# dds.net
KiCad netlist of a schematic drawn in EAGLE
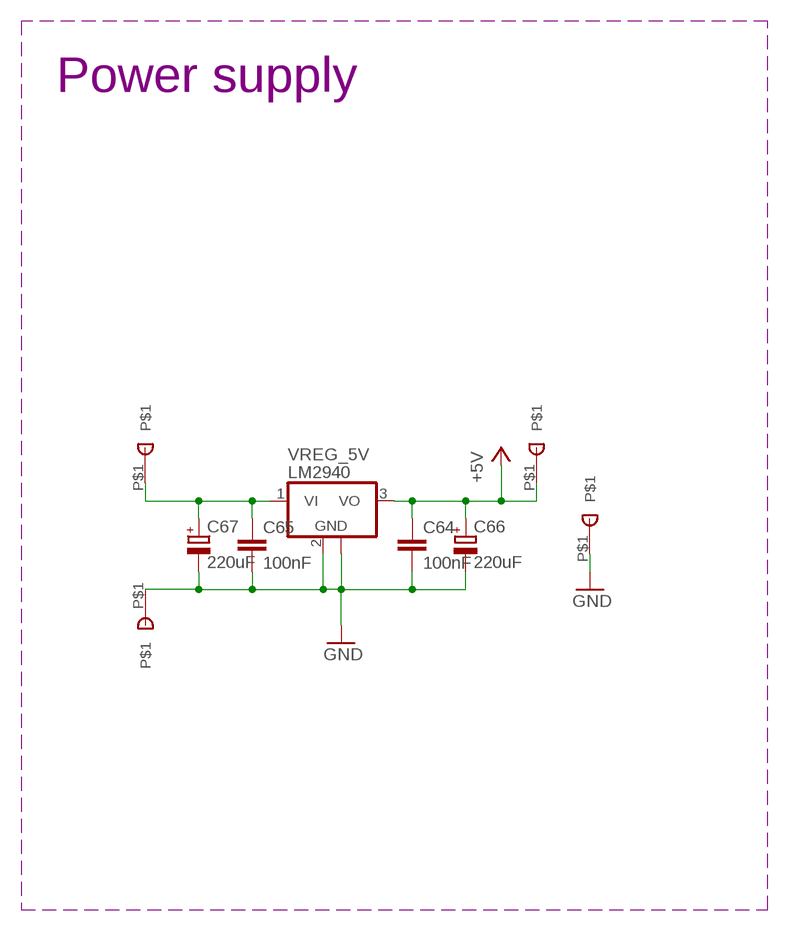
[diagram p0: schematic, sheet 1]
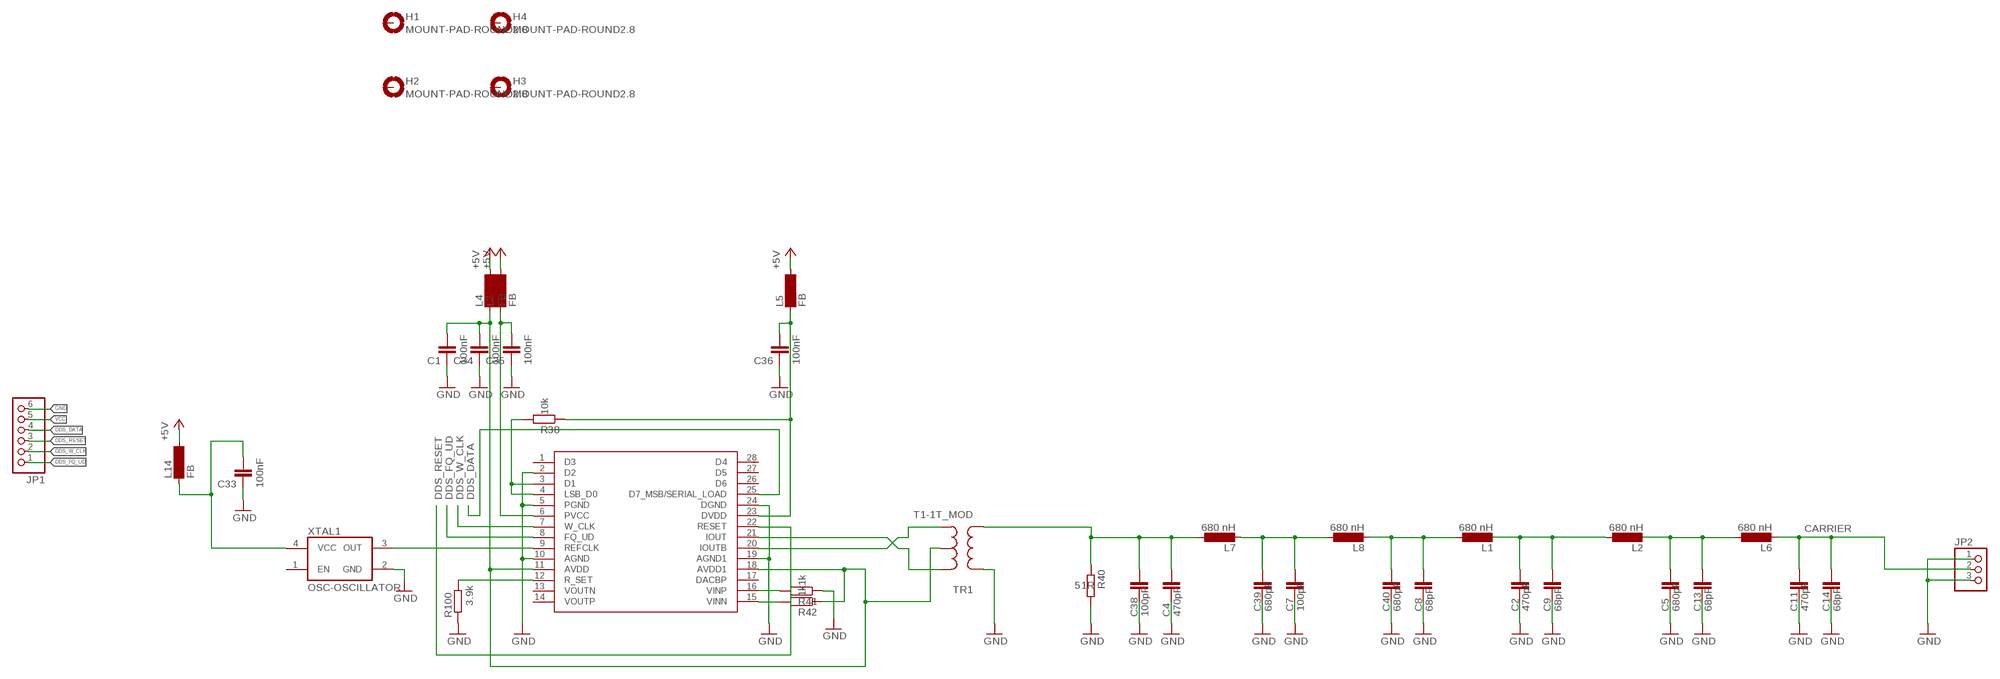
[diagram p1: schematic, sheet 2]

(export (version "E")
  (design (tool "Eeschema 10.0.6"))
  (components
    (comp (ref "C64")
      (value "100nF")
      (footprint "eagle-import:C0603")
      (libsource (lib "eagle-import") (part "C-EUC0603"))
    )
    (comp (ref "C65")
      (value "100nF")
      (footprint "eagle-import:C0603")
      (libsource (lib "eagle-import") (part "C-EUC0603"))
    )
    (comp (ref "C66")
      (value "220uF")
      (footprint "eagle-import:CT7343")
      (libsource (lib "eagle-import") (part "CPOL-EUCT7343"))
    )
    (comp (ref "C67")
      (value "220uF")
      (footprint "eagle-import:CT7343")
      (libsource (lib "eagle-import") (part "CPOL-EUCT7343"))
    )
    (comp (ref "U$3")
      (value "SINGLE_SMD_CONN_2.5X3.5")
      (footprint "eagle-import:SMD_CONN_2.5X3.5")
      (libsource (lib "eagle-import") (part "SINGLE_SMD_CONN_2.5X3.5"))
    )
    (comp (ref "U$8")
      (value "SINGLE_SMD_CONN_2.5X3.5")
      (footprint "eagle-import:SMD_CONN_2.5X3.5")
      (libsource (lib "eagle-import") (part "SINGLE_SMD_CONN_2.5X3.5"))
    )
    (comp (ref "U$22")
      (value "SINGLE_SMD_CONN_1.5X1.5")
      (footprint "eagle-import:SMD_CONN_1.5X1.5")
      (libsource (lib "eagle-import") (part "SINGLE_SMD_CONN_1.5X1.5"))
    )
    (comp (ref "U$23")
      (value "SINGLE_SMD_CONN_1.5X1.5")
      (footprint "eagle-import:SMD_CONN_1.5X1.5")
      (libsource (lib "eagle-import") (part "SINGLE_SMD_CONN_1.5X1.5"))
    )
    (comp (ref "VREG_5V")
      (value "LM2940")
      (footprint "eagle-import:SOT223")
      (libsource (lib "eagle-import") (part "UA78MDCY05"))
    )
    (comp (ref "C1")
      (value "100nF")
      (footprint "eagle-import:C0603K")
      (libsource (lib "eagle-import") (part "C-EUC0603K"))
    )
    (comp (ref "C2")
      (value "470pF")
      (footprint "eagle-import:C1206")
      (libsource (lib "eagle-import") (part "C-EUC1206"))
    )
    (comp (ref "C4")
      (value "470pF")
      (footprint "eagle-import:C1206")
      (libsource (lib "eagle-import") (part "C-EUC1206"))
    )
    (comp (ref "C5")
      (value "680pF")
      (footprint "eagle-import:C1206")
      (libsource (lib "eagle-import") (part "C-EUC1206"))
    )
    (comp (ref "C7")
      (value "100pF")
      (footprint "eagle-import:C1206")
      (libsource (lib "eagle-import") (part "C-EUC1206"))
    )
    (comp (ref "C8")
      (value "68pF")
      (footprint "eagle-import:C1206")
      (libsource (lib "eagle-import") (part "C-EUC1206"))
    )
    (comp (ref "C9")
      (value "68pF")
      (footprint "eagle-import:C1206")
      (libsource (lib "eagle-import") (part "C-EUC1206"))
    )
    (comp (ref "C11")
      (value "470pF")
      (footprint "eagle-import:C1206")
      (libsource (lib "eagle-import") (part "C-EUC1206"))
    )
    (comp (ref "C13")
      (value "68pF")
      (footprint "eagle-import:C1206")
      (libsource (lib "eagle-import") (part "C-EUC1206"))
    )
    (comp (ref "C14")
      (value "68pF")
      (footprint "eagle-import:C1206")
      (libsource (lib "eagle-import") (part "C-EUC1206"))
    )
    (comp (ref "C33")
      (value "100nF")
      (footprint "eagle-import:C0603K")
      (libsource (lib "eagle-import") (part "C-EUC0603K"))
    )
    (comp (ref "C34")
      (value "100nF")
      (footprint "eagle-import:C0603K")
      (libsource (lib "eagle-import") (part "C-EUC0603K"))
    )
    (comp (ref "C35")
      (value "100nF")
      (footprint "eagle-import:C0603K")
      (libsource (lib "eagle-import") (part "C-EUC0603K"))
    )
    (comp (ref "C36")
      (value "100nF")
      (footprint "eagle-import:C0603K")
      (libsource (lib "eagle-import") (part "C-EUC0603K"))
    )
    (comp (ref "C38")
      (value "100pF")
      (footprint "eagle-import:C1206")
      (libsource (lib "eagle-import") (part "C-EUC1206"))
    )
    (comp (ref "C39")
      (value "680pF")
      (footprint "eagle-import:C1206")
      (libsource (lib "eagle-import") (part "C-EUC1206"))
    )
    (comp (ref "C40")
      (value "680pF")
      (footprint "eagle-import:C1206")
      (libsource (lib "eagle-import") (part "C-EUC1206"))
    )
    (comp (ref "H1")
      (value "MOUNT-PAD-ROUND2.8")
      (footprint "eagle-import:2,8-PAD")
      (libsource (lib "eagle-import") (part "MOUNT-PAD-ROUND2.8"))
    )
    (comp (ref "H2")
      (value "MOUNT-PAD-ROUND2.8")
      (footprint "eagle-import:2,8-PAD")
      (libsource (lib "eagle-import") (part "MOUNT-PAD-ROUND2.8"))
    )
    (comp (ref "H3")
      (value "MOUNT-PAD-ROUND2.8")
      (footprint "eagle-import:2,8-PAD")
      (libsource (lib "eagle-import") (part "MOUNT-PAD-ROUND2.8"))
    )
    (comp (ref "H4")
      (value "MOUNT-PAD-ROUND2.8")
      (footprint "eagle-import:2,8-PAD")
      (libsource (lib "eagle-import") (part "MOUNT-PAD-ROUND2.8"))
    )
    (comp (ref "JP1")
      (value "PINHD-1X6")
      (footprint "eagle-import:1X06")
      (libsource (lib "eagle-import") (part "PINHD-1X6"))
    )
    (comp (ref "JP2")
      (value "PINHD-1X3")
      (footprint "eagle-import:1X03")
      (libsource (lib "eagle-import") (part "PINHD-1X3"))
    )
    (comp (ref "L1")
      (value "680 nH")
      (footprint "eagle-import:L1812")
      (libsource (lib "eagle-import") (part "L-EUL1812"))
    )
    (comp (ref "L2")
      (value "680 nH")
      (footprint "eagle-import:L1812")
      (libsource (lib "eagle-import") (part "L-EUL1812"))
    )
    (comp (ref "L3")
      (value "FB")
      (footprint "eagle-import:SM-1206")
      (libsource (lib "eagle-import") (part "SM-1206"))
    )
    (comp (ref "L4")
      (value "FB")
      (footprint "eagle-import:SM-1206")
      (libsource (lib "eagle-import") (part "SM-1206"))
    )
    (comp (ref "L5")
      (value "FB")
      (footprint "eagle-import:SM-1206")
      (libsource (lib "eagle-import") (part "SM-1206"))
    )
    (comp (ref "L6")
      (value "680 nH")
      (footprint "eagle-import:L1812")
      (libsource (lib "eagle-import") (part "L-EUL1812"))
    )
    (comp (ref "L7")
      (value "680 nH")
      (footprint "eagle-import:L1812")
      (libsource (lib "eagle-import") (part "L-EUL1812"))
    )
    (comp (ref "L8")
      (value "680 nH")
      (footprint "eagle-import:L1812")
      (libsource (lib "eagle-import") (part "L-EUL1812"))
    )
    (comp (ref "L14")
      (value "FB")
      (footprint "eagle-import:SM-1206")
      (libsource (lib "eagle-import") (part "SM-1206"))
    )
    (comp (ref "R38")
      (value "10k")
      (footprint "eagle-import:R0603")
      (libsource (lib "eagle-import") (part "R-EU_R0603"))
    )
    (comp (ref "R40")
      (value "51R")
      (footprint "eagle-import:R0603")
      (libsource (lib "eagle-import") (part "R-EU_R0603"))
    )
    (comp (ref "R41")
      (value "1k")
      (footprint "eagle-import:R0603")
      (libsource (lib "eagle-import") (part "R-EU_R0603"))
    )
    (comp (ref "R42")
      (value "1k")
      (footprint "eagle-import:R0603")
      (libsource (lib "eagle-import") (part "R-EU_R0603"))
    )
    (comp (ref "R100")
      (value "3.9k")
      (footprint "eagle-import:R0603")
      (libsource (lib "eagle-import") (part "R-EU_R0603"))
    )
    (comp (ref "TR1")
      (value "T1-1T_MOD")
      (footprint "eagle-import:KK81_MOD")
      (libsource (lib "eagle-import") (part "T1-1T_MOD"))
    )
    (comp (ref "U$9")
      (value "AD9851BR")
      (footprint "eagle-import:TSSOP28")
      (libsource (lib "eagle-import") (part "AD9851BR"))
    )
    (comp (ref "XTAL1")
      (value "OSC-OSCILLATOR")
      (footprint "eagle-import:OSCILLATOR_7X5_SMD")
      (libsource (lib "eagle-import") (part "OSC-OSCILLATOR"))
    )
  )
  (nets
    (net (code "1") (name "+5V") (class "Default")
      (node (ref "C64") (pin "1") (pinfunction "1_1") (pintype "passive"))
      (node (ref "C66") (pin "+") (pinfunction "+_+") (pintype "passive"))
      (node (ref "L14") (pin "2") (pinfunction "2_2") (pintype "passive"))
      (node (ref "L3") (pin "2") (pinfunction "2_2") (pintype "passive"))
      (node (ref "L4") (pin "2") (pinfunction "2_2") (pintype "passive"))
      (node (ref "L5") (pin "2") (pinfunction "2_2") (pintype "passive"))
      (node (ref "U$22") (pin "P$1") (pinfunction "P$1_P$1") (pintype "bidirectional"))
      (node (ref "VREG_5V") (pin "3") (pinfunction "VO_3") (pintype "passive"))
    )
    (net (code "2") (name "DDS_DATA") (class "Default")
      (node (ref "JP1") (pin "4") (pinfunction "4_4") (pintype "passive"))
      (node (ref "U$9") (pin "25") (pinfunction "D7_MSB/SERIAL_LOAD_25") (pintype "bidirectional"))
    )
    (net (code "3") (name "DDS_FQ_UD") (class "Default")
      (node (ref "JP1") (pin "1") (pinfunction "1_1") (pintype "passive"))
      (node (ref "U$9") (pin "8") (pinfunction "FQ_UD_8") (pintype "bidirectional"))
    )
    (net (code "4") (name "DDS_RESET") (class "Default")
      (node (ref "JP1") (pin "3") (pinfunction "3_3") (pintype "passive"))
      (node (ref "U$9") (pin "22") (pinfunction "RESET_22") (pintype "bidirectional"))
    )
    (net (code "5") (name "DDS_W_CLK") (class "Default")
      (node (ref "JP1") (pin "2") (pinfunction "2_2") (pintype "passive"))
      (node (ref "U$9") (pin "7") (pinfunction "W_CLK_7") (pintype "bidirectional"))
    )
    (net (code "6") (name "GND") (class "Default")
      (node (ref "C1") (pin "1") (pinfunction "1_1") (pintype "passive"))
      (node (ref "C11") (pin "1") (pinfunction "1_1") (pintype "passive"))
      (node (ref "C13") (pin "1") (pinfunction "1_1") (pintype "passive"))
      (node (ref "C14") (pin "1") (pinfunction "1_1") (pintype "passive"))
      (node (ref "C2") (pin "1") (pinfunction "1_1") (pintype "passive"))
      (node (ref "C33") (pin "1") (pinfunction "1_1") (pintype "passive"))
      (node (ref "C34") (pin "1") (pinfunction "1_1") (pintype "passive"))
      (node (ref "C35") (pin "1") (pinfunction "1_1") (pintype "passive"))
      (node (ref "C36") (pin "1") (pinfunction "1_1") (pintype "passive"))
      (node (ref "C38") (pin "1") (pinfunction "1_1") (pintype "passive"))
      (node (ref "C39") (pin "1") (pinfunction "1_1") (pintype "passive"))
      (node (ref "C4") (pin "1") (pinfunction "1_1") (pintype "passive"))
      (node (ref "C40") (pin "1") (pinfunction "1_1") (pintype "passive"))
      (node (ref "C5") (pin "1") (pinfunction "1_1") (pintype "passive"))
      (node (ref "C64") (pin "2") (pinfunction "2_2") (pintype "passive"))
      (node (ref "C65") (pin "2") (pinfunction "2_2") (pintype "passive"))
      (node (ref "C66") (pin "-") (pinfunction "-_-") (pintype "passive"))
      (node (ref "C67") (pin "-") (pinfunction "-_-") (pintype "passive"))
      (node (ref "C7") (pin "1") (pinfunction "1_1") (pintype "passive"))
      (node (ref "C8") (pin "1") (pinfunction "1_1") (pintype "passive"))
      (node (ref "C9") (pin "1") (pinfunction "1_1") (pintype "passive"))
      (node (ref "JP1") (pin "6") (pinfunction "6_6") (pintype "passive"))
      (node (ref "JP2") (pin "1") (pinfunction "1_1") (pintype "passive"))
      (node (ref "JP2") (pin "3") (pinfunction "3_3") (pintype "passive"))
      (node (ref "R100") (pin "1") (pinfunction "1_1") (pintype "passive"))
      (node (ref "R40") (pin "2") (pinfunction "2_2") (pintype "passive"))
      (node (ref "R41") (pin "1") (pinfunction "1_1") (pintype "passive"))
      (node (ref "TR1") (pin "1") (pinfunction "P1_1") (pintype "passive"))
      (node (ref "U$23") (pin "P$1") (pinfunction "P$1_P$1") (pintype "bidirectional"))
      (node (ref "U$3") (pin "P$1") (pinfunction "P$1_P$1") (pintype "bidirectional"))
      (node (ref "U$9") (pin "10") (pinfunction "AGND_10") (pintype "bidirectional"))
      (node (ref "U$9") (pin "19") (pinfunction "AGND1_19") (pintype "bidirectional"))
      (node (ref "U$9") (pin "2") (pinfunction "D2_2") (pintype "bidirectional"))
      (node (ref "U$9") (pin "24") (pinfunction "DGND_24") (pintype "bidirectional"))
      (node (ref "U$9") (pin "5") (pinfunction "PGND_5") (pintype "bidirectional"))
      (node (ref "VREG_5V") (pin "2") (pinfunction "GND_2") (pintype "passive"))
      (node (ref "VREG_5V") (pin "4") (pinfunction "GND_4") (pintype "passive"))
      (node (ref "XTAL1") (pin "2") (pinfunction "GND_2") (pintype "power_in"))
    )
    (net (code "7") (name "Net-(C2-Pad2)") (class "Default")
      (node (ref "C2") (pin "2") (pinfunction "2_2") (pintype "passive"))
      (node (ref "C9") (pin "2") (pinfunction "2_2") (pintype "passive"))
      (node (ref "L1") (pin "2") (pinfunction "2_2") (pintype "passive"))
      (node (ref "L2") (pin "1") (pinfunction "1_1") (pintype "passive"))
    )
    (net (code "8") (name "Net-(C11-Pad2)") (class "Default")
      (node (ref "C11") (pin "2") (pinfunction "2_2") (pintype "passive"))
      (node (ref "C14") (pin "2") (pinfunction "2_2") (pintype "passive"))
      (node (ref "JP2") (pin "2") (pinfunction "2_2") (pintype "passive"))
      (node (ref "L6") (pin "2") (pinfunction "2_2") (pintype "passive"))
    )
    (net (code "9") (name "Net-(C13-Pad2)") (class "Default")
      (node (ref "C13") (pin "2") (pinfunction "2_2") (pintype "passive"))
      (node (ref "C5") (pin "2") (pinfunction "2_2") (pintype "passive"))
      (node (ref "L2") (pin "2") (pinfunction "2_2") (pintype "passive"))
      (node (ref "L6") (pin "1") (pinfunction "1_1") (pintype "passive"))
    )
    (net (code "10") (name "Net-(C39-Pad2)") (class "Default")
      (node (ref "C39") (pin "2") (pinfunction "2_2") (pintype "passive"))
      (node (ref "C7") (pin "2") (pinfunction "2_2") (pintype "passive"))
      (node (ref "L7") (pin "2") (pinfunction "2_2") (pintype "passive"))
      (node (ref "L8") (pin "1") (pinfunction "1_1") (pintype "passive"))
    )
    (net (code "11") (name "Net-(C40-Pad2)") (class "Default")
      (node (ref "C40") (pin "2") (pinfunction "2_2") (pintype "passive"))
      (node (ref "C8") (pin "2") (pinfunction "2_2") (pintype "passive"))
      (node (ref "L1") (pin "1") (pinfunction "1_1") (pintype "passive"))
      (node (ref "L8") (pin "2") (pinfunction "2_2") (pintype "passive"))
    )
    (net (code "12") (name "Net-(TR1-P2)") (class "Default")
      (node (ref "C38") (pin "2") (pinfunction "2_2") (pintype "passive"))
      (node (ref "C4") (pin "2") (pinfunction "2_2") (pintype "passive"))
      (node (ref "L7") (pin "1") (pinfunction "1_1") (pintype "passive"))
      (node (ref "R40") (pin "1") (pinfunction "1_1") (pintype "passive"))
      (node (ref "TR1") (pin "3") (pinfunction "P2_3") (pintype "passive"))
    )
    (net (code "13") (name "Net-(TR1-S1)") (class "Default")
      (node (ref "TR1") (pin "6") (pinfunction "S1_6") (pintype "passive"))
      (node (ref "U$9") (pin "21") (pinfunction "IOUT_21") (pintype "bidirectional"))
    )
    (net (code "14") (name "Net-(TR1-S2)") (class "Default")
      (node (ref "TR1") (pin "4") (pinfunction "S2_4") (pintype "passive"))
      (node (ref "U$9") (pin "20") (pinfunction "IOUTB_20") (pintype "bidirectional"))
    )
    (net (code "15") (name "Net-(TR1-ST)") (class "Default")
      (node (ref "C1") (pin "2") (pinfunction "2_2") (pintype "passive"))
      (node (ref "C34") (pin "2") (pinfunction "2_2") (pintype "passive"))
      (node (ref "L4") (pin "1") (pinfunction "1_1") (pintype "passive"))
      (node (ref "R42") (pin "1") (pinfunction "1_1") (pintype "passive"))
      (node (ref "TR1") (pin "5") (pinfunction "ST_5") (pintype "passive"))
      (node (ref "U$9") (pin "11") (pinfunction "AVDD_11") (pintype "bidirectional"))
      (node (ref "U$9") (pin "18") (pinfunction "AVDD1_18") (pintype "bidirectional"))
    )
    (net (code "16") (name "Net-(U$9-D1)") (class "Default")
      (node (ref "R38") (pin "2") (pinfunction "2_2") (pintype "passive"))
      (node (ref "U$9") (pin "3") (pinfunction "D1_3") (pintype "bidirectional"))
      (node (ref "U$9") (pin "4") (pinfunction "LSB_D0_4") (pintype "bidirectional"))
    )
    (net (code "17") (name "Net-(U$9-DVDD)") (class "Default")
      (node (ref "C36") (pin "2") (pinfunction "2_2") (pintype "passive"))
      (node (ref "L5") (pin "1") (pinfunction "1_1") (pintype "passive"))
      (node (ref "R38") (pin "1") (pinfunction "1_1") (pintype "passive"))
      (node (ref "U$9") (pin "23") (pinfunction "DVDD_23") (pintype "bidirectional"))
    )
    (net (code "18") (name "Net-(U$9-PVCC)") (class "Default")
      (node (ref "C35") (pin "2") (pinfunction "2_2") (pintype "passive"))
      (node (ref "L3") (pin "1") (pinfunction "1_1") (pintype "passive"))
      (node (ref "U$9") (pin "6") (pinfunction "PVCC_6") (pintype "bidirectional"))
    )
    (net (code "19") (name "Net-(U$9-REFCLK)") (class "Default")
      (node (ref "U$9") (pin "9") (pinfunction "REFCLK_9") (pintype "bidirectional"))
      (node (ref "XTAL1") (pin "3") (pinfunction "OUT_3") (pintype "output"))
    )
    (net (code "20") (name "Net-(U$9-R_SET)") (class "Default")
      (node (ref "R100") (pin "2") (pinfunction "2_2") (pintype "passive"))
      (node (ref "U$9") (pin "12") (pinfunction "R_SET_12") (pintype "bidirectional"))
    )
    (net (code "21") (name "Net-(U$9-VINN)") (class "Default")
      (node (ref "R42") (pin "2") (pinfunction "2_2") (pintype "passive"))
      (node (ref "U$9") (pin "15") (pinfunction "VINN_15") (pintype "bidirectional"))
    )
    (net (code "22") (name "Net-(U$9-VINP)") (class "Default")
      (node (ref "R41") (pin "2") (pinfunction "2_2") (pintype "passive"))
      (node (ref "U$9") (pin "16") (pinfunction "VINP_16") (pintype "bidirectional"))
    )
    (net (code "23") (name "Net-(XTAL1-VCC)") (class "Default")
      (node (ref "C33") (pin "2") (pinfunction "2_2") (pintype "passive"))
      (node (ref "L14") (pin "1") (pinfunction "1_1") (pintype "passive"))
      (node (ref "XTAL1") (pin "4") (pinfunction "VCC_4") (pintype "power_in"))
    )
    (net (code "24") (name "VCC") (class "Default")
      (node (ref "C65") (pin "1") (pinfunction "1_1") (pintype "passive"))
      (node (ref "C67") (pin "+") (pinfunction "+_+") (pintype "passive"))
      (node (ref "JP1") (pin "5") (pinfunction "5_5") (pintype "passive"))
      (node (ref "U$8") (pin "P$1") (pinfunction "P$1_P$1") (pintype "bidirectional"))
      (node (ref "VREG_5V") (pin "1") (pinfunction "VI_1") (pintype "input"))
    )
    (net (code "25") (name "unconnected-(H1-MOUNT-PadB2,8)") (class "Default")
      (node (ref "H1") (pin "B2,8") (pinfunction "MOUNT_B2,8") (pintype "passive"))
    )
    (net (code "26") (name "unconnected-(H2-MOUNT-PadB2,8)") (class "Default")
      (node (ref "H2") (pin "B2,8") (pinfunction "MOUNT_B2,8") (pintype "passive"))
    )
    (net (code "27") (name "unconnected-(H3-MOUNT-PadB2,8)") (class "Default")
      (node (ref "H3") (pin "B2,8") (pinfunction "MOUNT_B2,8") (pintype "passive"))
    )
    (net (code "28") (name "unconnected-(H4-MOUNT-PadB2,8)") (class "Default")
      (node (ref "H4") (pin "B2,8") (pinfunction "MOUNT_B2,8") (pintype "passive"))
    )
    (net (code "29") (name "unconnected-(U$9-D3-Pad1)") (class "Default")
      (node (ref "U$9") (pin "1") (pinfunction "D3_1") (pintype "bidirectional"))
    )
    (net (code "30") (name "unconnected-(U$9-D4-Pad28)") (class "Default")
      (node (ref "U$9") (pin "28") (pinfunction "D4_28") (pintype "bidirectional"))
    )
    (net (code "31") (name "unconnected-(U$9-D5-Pad27)") (class "Default")
      (node (ref "U$9") (pin "27") (pinfunction "D5_27") (pintype "bidirectional"))
    )
    (net (code "32") (name "unconnected-(U$9-D6-Pad26)") (class "Default")
      (node (ref "U$9") (pin "26") (pinfunction "D6_26") (pintype "bidirectional"))
    )
    (net (code "33") (name "unconnected-(U$9-DACBP-Pad17)") (class "Default")
      (node (ref "U$9") (pin "17") (pinfunction "DACBP_17") (pintype "bidirectional"))
    )
    (net (code "34") (name "unconnected-(U$9-VOUTN-Pad13)") (class "Default")
      (node (ref "U$9") (pin "13") (pinfunction "VOUTN_13") (pintype "bidirectional"))
    )
    (net (code "35") (name "unconnected-(U$9-VOUTP-Pad14)") (class "Default")
      (node (ref "U$9") (pin "14") (pinfunction "VOUTP_14") (pintype "bidirectional"))
    )
    (net (code "36") (name "unconnected-(XTAL1-EN-Pad1)") (class "Default")
      (node (ref "XTAL1") (pin "1") (pinfunction "EN_1") (pintype "input"))
    )
  )
)
